# Gate_Driver.net
KiCad netlist of a schematic drawn in Altium Designer
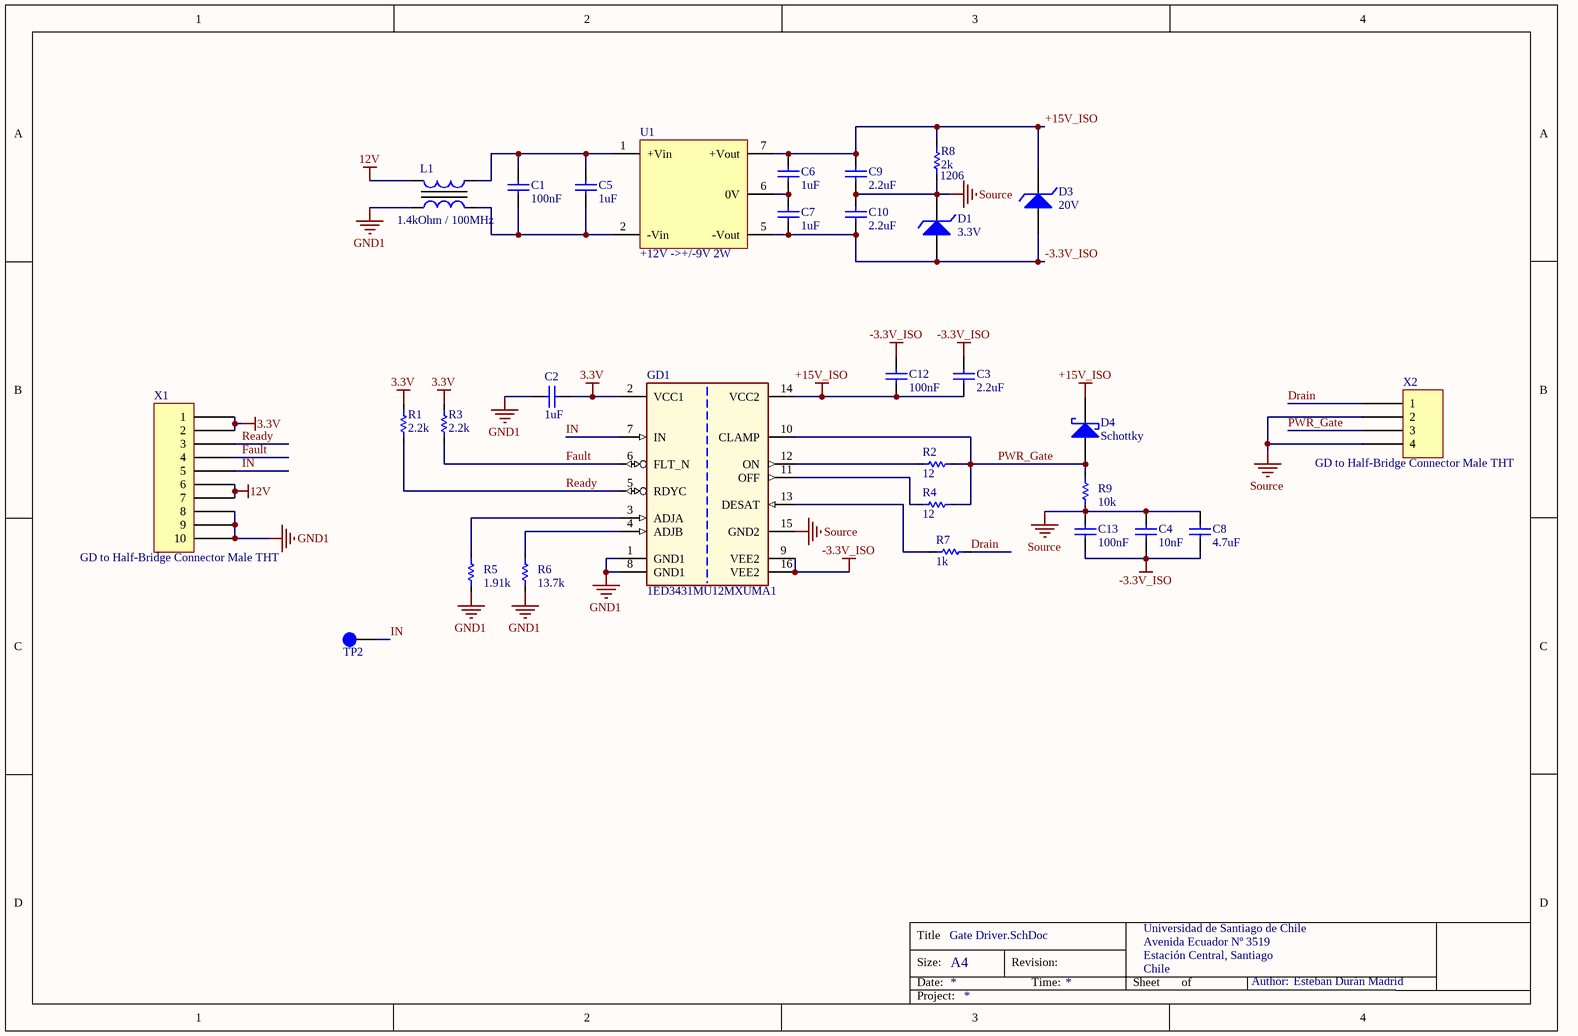
[diagram p0: Gate Driver.SchDoc]

(export (version "E")
  (design (tool "Eeschema 10.0.6"))
  (components
    (comp (ref "C1")
      (value "100nF")
      (footprint "CAP_0603")
      (description "0.1µF ±10% 50V Ceramic Capacitor X7R 0603 (1608 Metric)")
      (fields (field (name "MF") "KEMET") (field (name "CREATED") "2020_06_15_DAarancibia"))
      (libsource (lib "H-Bridge_Lib") (part "Cap_0603"))
    )
    (comp (ref "C2")
      (value "1uF")
      (footprint "CAP_0805")
      (description "0.1µF ±10% 50V Ceramic Capacitor X7R 0805 (2012 Metric)")
      (fields (field (name "MF") "KEMET") (field (name "CREATED") "2020_06_15_DAarancibia"))
      (libsource (lib "H-Bridge_Lib") (part "Cap_0805"))
    )
    (comp (ref "C3")
      (value "2.2uF")
      (footprint "CAP_0805")
      (description "0.1µF ±10% 50V Ceramic Capacitor X7R 0805 (2012 Metric)")
      (fields (field (name "MF") "Taiyo Yuden") (field (name "CREATED") "2020_06_15_DAarancibia"))
      (libsource (lib "Gate-Driver_Lib") (part "Cap_0805"))
    )
    (comp (ref "C4")
      (value "10nF")
      (footprint "CAP_0603")
      (description "±10% 50V Ceramic Capacitor X7R 0603 (1608 Metric)")
      (fields (field (name "MF") "KEMET") (field (name "CREATED") "2020_06_15_DAarancibia"))
      (libsource (lib "H-Bridge_Lib") (part "Cap_0603"))
    )
    (comp (ref "C5")
      (value "1uF")
      (footprint "CAP_0805")
      (description "0.1µF ±10% 50V Ceramic Capacitor X7R 0805 (2012 Metric)")
      (fields (field (name "MF") "KEMET") (field (name "CREATED") "2020_06_15_DAarancibia"))
      (libsource (lib "H-Bridge_Lib") (part "Cap_0805"))
    )
    (comp (ref "C6")
      (value "1uF")
      (footprint "CAP_0805")
      (description "0.1µF ±10% 50V Ceramic Capacitor X7R 0805 (2012 Metric)")
      (fields (field (name "MF") "KEMET") (field (name "CREATED") "2020_06_15_DAarancibia"))
      (libsource (lib "H-Bridge_Lib") (part "Cap_0805"))
    )
    (comp (ref "C7")
      (value "1uF")
      (footprint "CAP_0805")
      (description "0.1µF ±10% 50V Ceramic Capacitor X7R 0805 (2012 Metric)")
      (fields (field (name "MF") "KEMET") (field (name "CREATED") "2020_06_15_DAarancibia"))
      (libsource (lib "H-Bridge_Lib") (part "Cap_0805"))
    )
    (comp (ref "C8")
      (value "4.7uF")
      (footprint "CAP_0805")
      (description "4.7 µF ±10% 50V Ceramic Capacitor X7R 0805 (2012 Metric)")
      (fields (field (name "MF") "Murata Electronics") (field (name "CREATED") "2020_06_15_DAarancibia"))
      (libsource (lib "Gate-Driver_Lib") (part "Cap_0805"))
    )
    (comp (ref "C9")
      (value "2.2uF")
      (footprint "CAP_0805")
      (description "2.2µF ±10% 50V Ceramic Capacitor X7R 0805 (2012 Metric)")
      (fields (field (name "MF") "KEMET") (field (name "CREATED") "2020_06_15_DAarancibia"))
      (libsource (lib "H-Bridge_Lib") (part "Cap_0805"))
    )
    (comp (ref "C10")
      (value "2.2uF")
      (footprint "CAP_0805")
      (description "2.2µF ±10% 50V Ceramic Capacitor X7R 0805 (2012 Metric)")
      (fields (field (name "MF") "KEMET") (field (name "CREATED") "2020_06_15_DAarancibia"))
      (libsource (lib "H-Bridge_Lib") (part "Cap_0805"))
    )
    (comp (ref "C12")
      (value "100nF")
      (footprint "CAP_0603")
      (description "0.1µF ±10% 50V Ceramic Capacitor X7R 0603 (1608 Metric)")
      (fields (field (name "MF") "KEMET") (field (name "CREATED") "2020_06_15_DAarancibia"))
      (libsource (lib "H-Bridge_Lib") (part "Cap_0603"))
    )
    (comp (ref "C13")
      (value "100nF")
      (footprint "CAP_0603")
      (description "0.1µF ±10% 50V Ceramic Capacitor X7R 0603 (1608 Metric)")
      (fields (field (name "MF") "KEMET") (field (name "CREATED") "2020_06_15_DAarancibia"))
      (libsource (lib "H-Bridge_Lib") (part "Cap_0603"))
    )
    (comp (ref "D1")
      (value "3.3V")
      (footprint "SOD-123")
      (description "Zener Diode 3.3V 500mW ±5% Surface Mount SOD-123")
      (fields (field (name "MF") "ON Semiconductor") (field (name "CREATED") "2020_07_28_DAarancibia"))
      (libsource (lib "H-Bridge_Lib") (part "Diode_Zener_3.3V"))
    )
    (comp (ref "D3")
      (value "20V")
      (footprint "SOD-123")
      (description "Zener Diode 20V 500mW ±5% Surface Mount SOD-123")
      (fields (field (name "MF") "Micro Commercial Co") (field (name "CREATED") "2020_07_28_DAarancibia"))
      (libsource (lib "H-Bridge_Lib") (part "Diode_Zener_20V"))
    )
    (comp (ref "D4")
      (value "Schottky")
      (footprint "SOD-123")
      (description "Diode Schottky 30 V 1A Surface Mount PG-SOD323-2")
      (fields (field (name "MF") "Infineon Technologies") (field (name "CREATED") "2021_05_16_EDuran"))
      (libsource (lib "Gate-Driver_Lib") (part "Diode_Schottky_30V/1A"))
    )
    (comp (ref "GD1")
      (value "1ED3431MU12MXUMA1")
      (footprint "SOP65P1030X265-16N-1")
      (description "3A Gate Driver Capacitive Coupling - Channel PG-DSO-16-28")
      (fields (field (name "MF") "Infineon Technologies") (field (name "CREATED") "2021_05_15_EDuran"))
      (libsource (lib "Gate-Driver_Lib") (part "1ED3431MU12M"))
    )
    (comp (ref "L1")
      (value "1.4kOhm / 100MHz")
      (footprint "CHOKE_CM_4.7x4.5mm")
      (description "2 Line Common Mode Choke Surface Mount 1.4 kOhms @ 100MHz 1.7A DCR 80mOhm")
      (fields (field (name "MF") "TDK Corporation") (field (name "CREATED") "2020_07_28_DAarancibia"))
      (libsource (lib "H-Bridge_Lib") (part "Choke_CM_ACM4520"))
    )
    (comp (ref "R1")
      (value "2.2k")
      (footprint "RES_0603")
      (description "2.2 kOhms ±5% 0.1W, 1/10W Chip Resistor 0603 (1608 Metric) Moisture Resistant Thick Film")
      (fields (field (name "MF") "Bourns Inc.") (field (name "CREATED") "2020_06_15_DAarancibia"))
      (libsource (lib "Gate-Driver_Lib") (part "Res_0603"))
    )
    (comp (ref "R2")
      (value "12")
      (footprint "RES_MMB_0207")
      (description "12 Ohms ±1% 1W Chip Resistor MELF, 0207 Anti-Sulfur, Automotive AEC-Q200 Thin Film")
      (fields (field (name "MF") "Vishay Beyschlag") (field (name "CREATED") "2020_06_15_DAarancibia"))
      (libsource (lib "H-Bridge_Lib") (part "Res_MELF_0207"))
    )
    (comp (ref "R3")
      (value "2.2k")
      (footprint "RES_0603")
      (description "2.2 kOhms ±5% 0.1W, 1/10W Chip Resistor 0603 (1608 Metric) Moisture Resistant Thick Film")
      (fields (field (name "MF") "Bourns Inc.") (field (name "CREATED") "2020_06_15_DAarancibia"))
      (libsource (lib "Gate-Driver_Lib") (part "Res_0603"))
    )
    (comp (ref "R4")
      (value "12")
      (footprint "RES_MMB_0207")
      (description "12 Ohms ±1% 1W Chip Resistor MELF, 0207 Anti-Sulfur, Automotive AEC-Q200 Thin Film")
      (fields (field (name "MF") "Vishay Beyschlag") (field (name "CREATED") "2020_06_15_DAarancibia"))
      (libsource (lib "H-Bridge_Lib") (part "Res_MELF_0207"))
    )
    (comp (ref "R5")
      (value "1.91k")
      (footprint "RES_0603")
      (description "1.91 kOhms ±1% 0.1W, 1/10W Chip Resistor 0603 (1608 Metric) Moisture Resistant Thick Film")
      (fields (field (name "MF") "Yageo") (field (name "CREATED") "2020_06_15_DAarancibia"))
      (libsource (lib "Gate-Driver_Lib") (part "Res_0603"))
    )
    (comp (ref "R6")
      (value "13.7k")
      (footprint "RES_0603")
      (description "13.7 kOhms ±1% 0.1W, 1/10W Chip Resistor 0603 (1608 Metric) Automotive AEC-Q200 Thick Film")
      (fields
        (field (name "MF") "Stackpole Electronics Inc")
        (field (name "CREATED") "2020_06_15_DAarancibia")
      )
      (libsource (lib "Gate-Driver_Lib") (part "Res_0603"))
    )
    (comp (ref "R7")
      (value "1k")
      (footprint "RES_0603")
      (fields (field (name "MF") "Yageo") (field (name "CREATED") "2020_06_15_DAarancibia"))
      (libsource (lib "H-Bridge_Lib") (part "Res_0603"))
    )
    (comp (ref "R8")
      (value "2k")
      (footprint "RES_1206")
      (description "2 kOhms ±0.1% 0.25W, 1/4W Chip Resistor 1206 (3216 Metric) - Thin Film")
      (fields
        (field (name "MF") "Yageo")
        (field (name "PACKAGE") "1206")
        (field (name "CREATED") "2020_06_15_DAarancibia")
      )
      (libsource (lib "H-Bridge_Lib") (part "Res_1206"))
    )
    (comp (ref "R9")
      (value "10k")
      (footprint "RES_0603")
      (description "10 kOhms ±5% 0.1W, 1/10W Chip Resistor 0603 (1608 Metric) Moisture Resistant Thick Film")
      (fields (field (name "MF") "Yageo") (field (name "CREATED") "2020_06_15_DAarancibia"))
      (libsource (lib "H-Bridge_Lib") (part "Res_0603"))
    )
    (comp (ref "TP2")
      (value "Gate")
      (footprint "TP_1mm")
      (description "Testpoint 1mm")
      (fields (field (name "CREATED") "2018_06_25_AGeiger"))
      (libsource (lib "H-Bridge_Lib") (part "TP_1mm"))
    )
    (comp (ref "U1")
      (value "+12V ->+/-9V 2W")
      (footprint "DC//DC MEJ2D0509SC")
      (description "Isolated Module DC DC Converter 2 Output 9V -9V - 111mA, 111mA 10.8V - 13.2V Input")
      (fields
        (field (name "MF") "Murata Power Solutions Inc.")
        (field (name "MPN") "MEJ2D1209SC")
        (field (name "CREATED") "2021_05_17_EDuran")
      )
      (libsource (lib "Gate-Driver_Lib") (part "DC//DC MEJ2D1209SC"))
    )
    (comp (ref "X1")
      (value "GD to Half-Bridge Connector Male THT")
      (footprint "TMM-110-01-G-S")
      (description "Connector Header Through Hole 10 position 0.079\" (2.00mm)")
      (fields
        (field (name "MF") "Samtec Inc.")
        (field (name "MPN") "TMM-110-01-G-S")
        (field (name "CREATED") "2021_05_24_EDuran")
      )
      (libsource (lib "Gate-Driver_Lib") (part "Con_Header_Male_6"))
    )
    (comp (ref "X2")
      (value "GD to Half-Bridge Connector Male THT")
      (footprint "TMM-104-01-G-S")
      (description "Connector Header Through Hole 4 position 0.079\" (2.00mm)")
      (fields
        (field (name "MF") "Samtec Inc.")
        (field (name "MPN") "TMM-104-01-G-S")
        (field (name "CREATED") "2021_05_24_EDuran")
      )
      (libsource (lib "Gate-Driver_Lib") (part "Con_Header_Male_5"))
    )
  )
  (nets
    (net (code "1") (name "+15V_ISO") (class "Default")
      (node (ref "C12") (pin "2") (pinfunction "2_2") (pintype "passive"))
      (node (ref "C3") (pin "2") (pinfunction "2_2") (pintype "passive"))
      (node (ref "C6") (pin "1") (pinfunction "1_1") (pintype "passive"))
      (node (ref "C9") (pin "1") (pinfunction "1_1") (pintype "passive"))
      (node (ref "D3") (pin "K") (pinfunction "K_K") (pintype "passive"))
      (node (ref "D4") (pin "K") (pinfunction "K_K") (pintype "passive"))
      (node (ref "GD1") (pin "14") (pinfunction "VCC2_14") (pintype "power_in"))
      (node (ref "R8") (pin "2") (pinfunction "2_2") (pintype "passive"))
      (node (ref "U1") (pin "7") (pinfunction "+Vout_7") (pintype "passive"))
    )
    (net (code "2") (name "-3.3V_ISO") (class "Default")
      (node (ref "C10") (pin "2") (pinfunction "2_2") (pintype "passive"))
      (node (ref "C12") (pin "1") (pinfunction "1_1") (pintype "passive"))
      (node (ref "C13") (pin "2") (pinfunction "2_2") (pintype "passive"))
      (node (ref "C3") (pin "1") (pinfunction "1_1") (pintype "passive"))
      (node (ref "C4") (pin "2") (pinfunction "2_2") (pintype "passive"))
      (node (ref "C7") (pin "2") (pinfunction "2_2") (pintype "passive"))
      (node (ref "C8") (pin "2") (pinfunction "2_2") (pintype "passive"))
      (node (ref "D1") (pin "A") (pinfunction "A_A") (pintype "passive"))
      (node (ref "D3") (pin "A") (pinfunction "A_A") (pintype "passive"))
      (node (ref "GD1") (pin "16") (pinfunction "VEE2_16") (pintype "power_in"))
      (node (ref "GD1") (pin "9") (pinfunction "VEE2_9") (pintype "power_in"))
      (node (ref "U1") (pin "5") (pinfunction "-Vout_5") (pintype "passive"))
    )
    (net (code "3") (name "/Drain") (class "Default")
      (node (ref "R7") (pin "2") (pinfunction "2_2") (pintype "passive"))
      (node (ref "X2") (pin "1") (pinfunction "1_1") (pintype "passive"))
    )
    (net (code "4") (name "/Fault") (class "Default")
      (node (ref "GD1") (pin "6") (pinfunction "FLT_N_6") (pintype "bidirectional"))
      (node (ref "R3") (pin "1") (pinfunction "1_1") (pintype "passive"))
      (node (ref "X1") (pin "4") (pinfunction "4_4") (pintype "passive"))
    )
    (net (code "5") (name "/IN") (class "Default")
      (node (ref "GD1") (pin "7") (pinfunction "IN_7") (pintype "input"))
      (node (ref "TP2") (pin "1") (pintype "passive"))
      (node (ref "X1") (pin "5") (pinfunction "5_5") (pintype "passive"))
    )
    (net (code "6") (name "/PWR_Gate") (class "Default")
      (node (ref "D4") (pin "A") (pinfunction "A_A") (pintype "passive"))
      (node (ref "GD1") (pin "10") (pinfunction "CLAMP_10") (pintype "passive"))
      (node (ref "R2") (pin "1") (pinfunction "1_1") (pintype "passive"))
      (node (ref "R4") (pin "1") (pinfunction "1_1") (pintype "passive"))
      (node (ref "R9") (pin "2") (pinfunction "2_2") (pintype "passive"))
      (node (ref "X2") (pin "3") (pinfunction "3_3") (pintype "passive"))
    )
    (net (code "7") (name "/Ready") (class "Default")
      (node (ref "GD1") (pin "5") (pinfunction "RDYC_5") (pintype "bidirectional"))
      (node (ref "R1") (pin "1") (pinfunction "1_1") (pintype "passive"))
      (node (ref "X1") (pin "3") (pinfunction "3_3") (pintype "passive"))
    )
    (net (code "8") (name "3.3V") (class "Default")
      (node (ref "C2") (pin "1") (pinfunction "1_1") (pintype "passive"))
      (node (ref "GD1") (pin "2") (pinfunction "VCC1_2") (pintype "power_in"))
      (node (ref "R1") (pin "2") (pinfunction "2_2") (pintype "passive"))
      (node (ref "R3") (pin "2") (pinfunction "2_2") (pintype "passive"))
      (node (ref "X1") (pin "1") (pinfunction "1_1") (pintype "passive"))
      (node (ref "X1") (pin "2") (pinfunction "2_2") (pintype "passive"))
    )
    (net (code "9") (name "12V") (class "Default")
      (node (ref "L1") (pin "3") (pinfunction "3_3") (pintype "passive"))
      (node (ref "X1") (pin "6") (pinfunction "6_6") (pintype "passive"))
      (node (ref "X1") (pin "7") (pinfunction "7_7") (pintype "passive"))
    )
    (net (code "10") (name "GND1") (class "Default")
      (node (ref "C2") (pin "2") (pinfunction "2_2") (pintype "passive"))
      (node (ref "GD1") (pin "1") (pinfunction "GND1_1") (pintype "power_in"))
      (node (ref "GD1") (pin "8") (pinfunction "GND1_8") (pintype "power_in"))
      (node (ref "L1") (pin "4") (pinfunction "4_4") (pintype "passive"))
      (node (ref "R5") (pin "1") (pinfunction "1_1") (pintype "passive"))
      (node (ref "R6") (pin "1") (pinfunction "1_1") (pintype "passive"))
      (node (ref "X1") (pin "10") (pinfunction "10_10") (pintype "passive"))
      (node (ref "X1") (pin "8") (pinfunction "8_8") (pintype "passive"))
      (node (ref "X1") (pin "9") (pinfunction "9_9") (pintype "passive"))
    )
    (net (code "11") (name "Net-(GD1-ADJA)") (class "Default")
      (node (ref "GD1") (pin "3") (pinfunction "ADJA_3") (pintype "input"))
      (node (ref "R5") (pin "2") (pinfunction "2_2") (pintype "passive"))
    )
    (net (code "12") (name "Net-(GD1-ADJB)") (class "Default")
      (node (ref "GD1") (pin "4") (pinfunction "ADJB_4") (pintype "input"))
      (node (ref "R6") (pin "2") (pinfunction "2_2") (pintype "passive"))
    )
    (net (code "13") (name "Net-(GD1-DESAT)") (class "Default")
      (node (ref "GD1") (pin "13") (pinfunction "DESAT_13") (pintype "input"))
      (node (ref "R7") (pin "1") (pinfunction "1_1") (pintype "passive"))
    )
    (net (code "14") (name "Net-(GD1-OFF)") (class "Default")
      (node (ref "GD1") (pin "11") (pinfunction "OFF_11") (pintype "output"))
      (node (ref "R4") (pin "2") (pinfunction "2_2") (pintype "passive"))
    )
    (net (code "15") (name "Net-(GD1-ON)") (class "Default")
      (node (ref "GD1") (pin "12") (pinfunction "ON_12") (pintype "output"))
      (node (ref "R2") (pin "2") (pinfunction "2_2") (pintype "passive"))
    )
    (net (code "16") (name "Net-(U1-+Vin)") (class "Default")
      (node (ref "C1") (pin "2") (pinfunction "2_2") (pintype "passive"))
      (node (ref "C5") (pin "1") (pinfunction "1_1") (pintype "passive"))
      (node (ref "L1") (pin "2") (pinfunction "2_2") (pintype "passive"))
      (node (ref "U1") (pin "1") (pinfunction "+Vin_1") (pintype "passive"))
    )
    (net (code "17") (name "Net-(U1--Vin)") (class "Default")
      (node (ref "C1") (pin "1") (pinfunction "1_1") (pintype "passive"))
      (node (ref "C5") (pin "2") (pinfunction "2_2") (pintype "passive"))
      (node (ref "L1") (pin "1") (pinfunction "1_1") (pintype "passive"))
      (node (ref "U1") (pin "2") (pinfunction "-Vin_2") (pintype "passive"))
    )
    (net (code "18") (name "Net-(U1-0V)") (class "Default")
      (node (ref "C6") (pin "2") (pinfunction "2_2") (pintype "passive"))
      (node (ref "C7") (pin "1") (pinfunction "1_1") (pintype "passive"))
      (node (ref "U1") (pin "6") (pinfunction "0V_6") (pintype "passive"))
    )
    (net (code "19") (name "Source") (class "Default")
      (node (ref "C10") (pin "1") (pinfunction "1_1") (pintype "passive"))
      (node (ref "C13") (pin "1") (pinfunction "1_1") (pintype "passive"))
      (node (ref "C4") (pin "1") (pinfunction "1_1") (pintype "passive"))
      (node (ref "C8") (pin "1") (pinfunction "1_1") (pintype "passive"))
      (node (ref "C9") (pin "2") (pinfunction "2_2") (pintype "passive"))
      (node (ref "D1") (pin "K") (pinfunction "K_K") (pintype "passive"))
      (node (ref "GD1") (pin "15") (pinfunction "GND2_15") (pintype "power_in"))
      (node (ref "R8") (pin "1") (pinfunction "1_1") (pintype "passive"))
      (node (ref "R9") (pin "1") (pinfunction "1_1") (pintype "passive"))
      (node (ref "X2") (pin "2") (pinfunction "2_2") (pintype "passive"))
      (node (ref "X2") (pin "4") (pinfunction "4_4") (pintype "passive"))
    )
  )
)
